# Stepper_Driver.net
KiCad netlist of a schematic drawn in Altium Designer
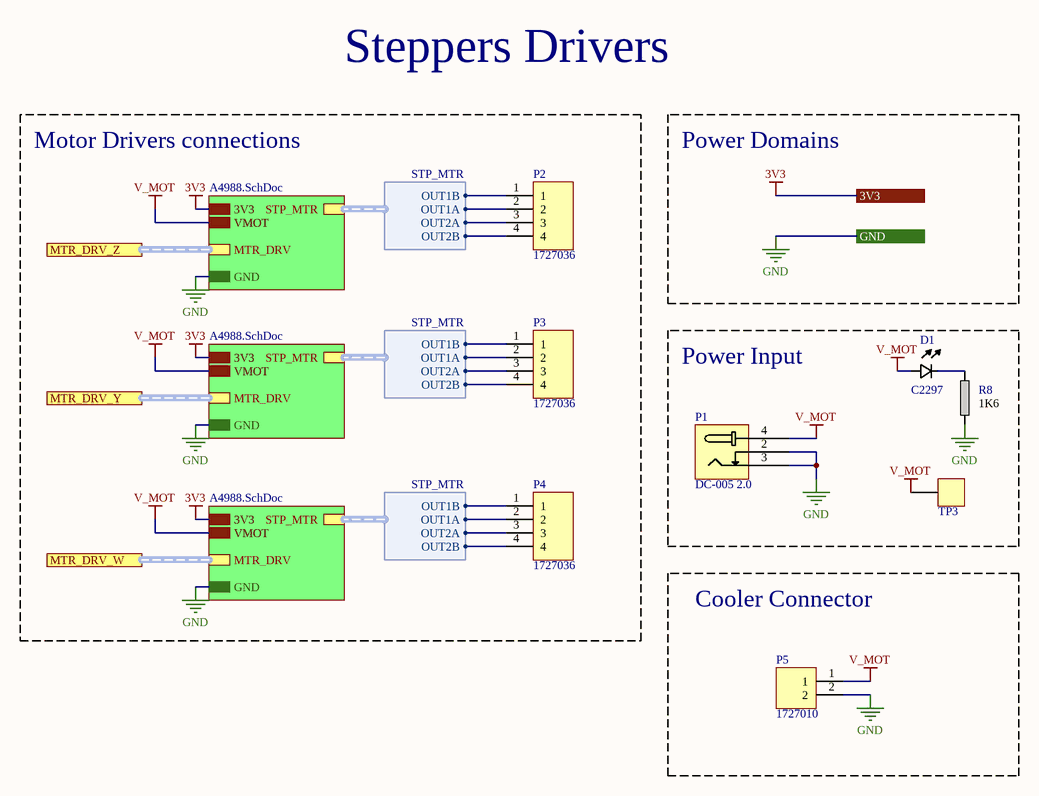
[diagram p0: Stepper_Driver.SchDoc]

(export (version "E")
  (design (tool "Eeschema 10.0.6"))
  (components
    (comp (ref "D1")
      (value "LED")
      (footprint "0805")
      (description "0805 Light Emitting Diodes (LED) ROHS")
      (fields
        (field (name "MANUFACTURER") "Hubei KENTO Elec")
        (field (name "MANUFACTURER PART NUMBER") "C2297")
      )
      (libsource (lib "Library") (part "LED"))
    )
    (comp (ref "P1")
      (value "DC-005 2.0")
      (footprint "DC-005 2.0")
      (description "Shrouded DC Power Receptacle 2mm 6.4mm Plugin AC/DC Power Connectors ROHS")
      (fields
        (field (name "MANUFACTURER") "BOOMELE(Boom Precision Elec)")
        (field (name "MANUFACTURER PART NUMBER") "DC-005 2.0")
      )
      (libsource (lib "Library") (part "DC-005 2.0"))
    )
    (comp (ref "P2")
      (value "MOTOR Z")
      (footprint "1727036")
      (description "TERM BLK 4P SIDE ENT 3.81MM PCB")
      (fields
        (field (name "MANUFACTURER") "Phoenix Contact")
        (field (name "MANUFACTURER PART NUMBER") "1727036")
      )
      (libsource (lib "Library") (part "BORNERA SR-4"))
    )
    (comp (ref "P3")
      (value "MOTOR Y")
      (footprint "1727036")
      (description "TERM BLK 4P SIDE ENT 3.81MM PCB")
      (fields
        (field (name "MANUFACTURER") "Phoenix Contact")
        (field (name "MANUFACTURER PART NUMBER") "1727036")
      )
      (libsource (lib "Library") (part "BORNERA SR-4"))
    )
    (comp (ref "P4")
      (value "MOTOR W")
      (footprint "1727036")
      (description "TERM BLK 4P SIDE ENT 3.81MM PCB")
      (fields
        (field (name "MANUFACTURER") "Phoenix Contact")
        (field (name "MANUFACTURER PART NUMBER") "1727036")
      )
      (libsource (lib "Library") (part "BORNERA SR-4"))
    )
    (comp (ref "P5")
      (value "BORNERA SR-2")
      (footprint "1727010")
      (description "TERM BLK 2P SIDE ENT 3.81MM PCB")
      (fields
        (field (name "MANUFACTURER") "Phoenix Contact")
        (field (name "MANUFACTURER PART NUMBER") "1727010")
      )
      (libsource (lib "Library") (part "BORNERA SR-2"))
    )
    (comp (ref "R8")
      (value "1K6")
      (footprint "0805")
      (description "125mW Thick Film Resistors ±1% 1.6kΩ 0805  Chip Resistor - Surface Mount ROHS")
      (fields
        (field (name "MANUFACTURER") "Resistor.Today")
        (field (name "MANUFACTURER PART NUMBER") "AECR0805F1K60K9")
      )
      (libsource (lib "Library") (part "RES"))
    )
    (comp (ref "TP3")
      (value "12V")
      (footprint "5015")
      (description "Thimble/Copper Rod/Test Ring ROHS")
      (fields (field (name "MANUFACTURER") "Ronghe") (field (name "MANUFACTURER PART NUMBER") "RH-5015"))
      (libsource (lib "Library") (part "TESTPOINT_5015"))
    )
  )
  (nets
    (net (code "10") (name "GND") (class "Default")
      (node (ref "P1") (pin "2") (pinfunction "2_2") (pintype "passive"))
      (node (ref "P1") (pin "3") (pinfunction "3_3") (pintype "passive"))
      (node (ref "P5") (pin "2") (pinfunction "2_2") (pintype "passive"))
      (node (ref "R8") (pin "1") (pinfunction "1_1") (pintype "passive"))
    )
    (net (code "11") (name "Net-(D1-Pad2)") (class "Default")
      (node (ref "D1") (pin "2") (pinfunction "2_2") (pintype "passive"))
      (node (ref "R8") (pin "2") (pinfunction "2_2") (pintype "passive"))
    )
    (net (code "12") (name "V_MOT") (class "Default")
      (node (ref "D1") (pin "1") (pinfunction "1_1") (pintype "passive"))
      (node (ref "P1") (pin "4") (pinfunction "4_4") (pintype "passive"))
      (node (ref "P5") (pin "1") (pinfunction "1_1") (pintype "passive"))
      (node (ref "TP3") (pin "1") (pinfunction "1_1") (pintype "passive"))
    )
    (net (code "13") (name "unconnected-(P2-Pad1)") (class "Default")
      (node (ref "P2") (pin "1") (pinfunction "1_1") (pintype "passive"))
    )
    (net (code "14") (name "unconnected-(P2-Pad2)") (class "Default")
      (node (ref "P2") (pin "2") (pinfunction "2_2") (pintype "passive"))
    )
    (net (code "15") (name "unconnected-(P2-Pad3)") (class "Default")
      (node (ref "P2") (pin "3") (pinfunction "3_3") (pintype "passive"))
    )
    (net (code "16") (name "unconnected-(P2-Pad4)") (class "Default")
      (node (ref "P2") (pin "4") (pinfunction "4_4") (pintype "passive"))
    )
    (net (code "17") (name "unconnected-(P3-Pad1)") (class "Default")
      (node (ref "P3") (pin "1") (pinfunction "1_1") (pintype "passive"))
    )
    (net (code "18") (name "unconnected-(P3-Pad2)") (class "Default")
      (node (ref "P3") (pin "2") (pinfunction "2_2") (pintype "passive"))
    )
    (net (code "19") (name "unconnected-(P3-Pad3)") (class "Default")
      (node (ref "P3") (pin "3") (pinfunction "3_3") (pintype "passive"))
    )
    (net (code "20") (name "unconnected-(P3-Pad4)") (class "Default")
      (node (ref "P3") (pin "4") (pinfunction "4_4") (pintype "passive"))
    )
    (net (code "21") (name "unconnected-(P4-Pad1)") (class "Default")
      (node (ref "P4") (pin "1") (pinfunction "1_1") (pintype "passive"))
    )
    (net (code "22") (name "unconnected-(P4-Pad2)") (class "Default")
      (node (ref "P4") (pin "2") (pinfunction "2_2") (pintype "passive"))
    )
    (net (code "23") (name "unconnected-(P4-Pad3)") (class "Default")
      (node (ref "P4") (pin "3") (pinfunction "3_3") (pintype "passive"))
    )
    (net (code "24") (name "unconnected-(P4-Pad4)") (class "Default")
      (node (ref "P4") (pin "4") (pinfunction "4_4") (pintype "passive"))
    )
  )
)
